# line_kick.net
KiCad netlist of a schematic drawn in EAGLE
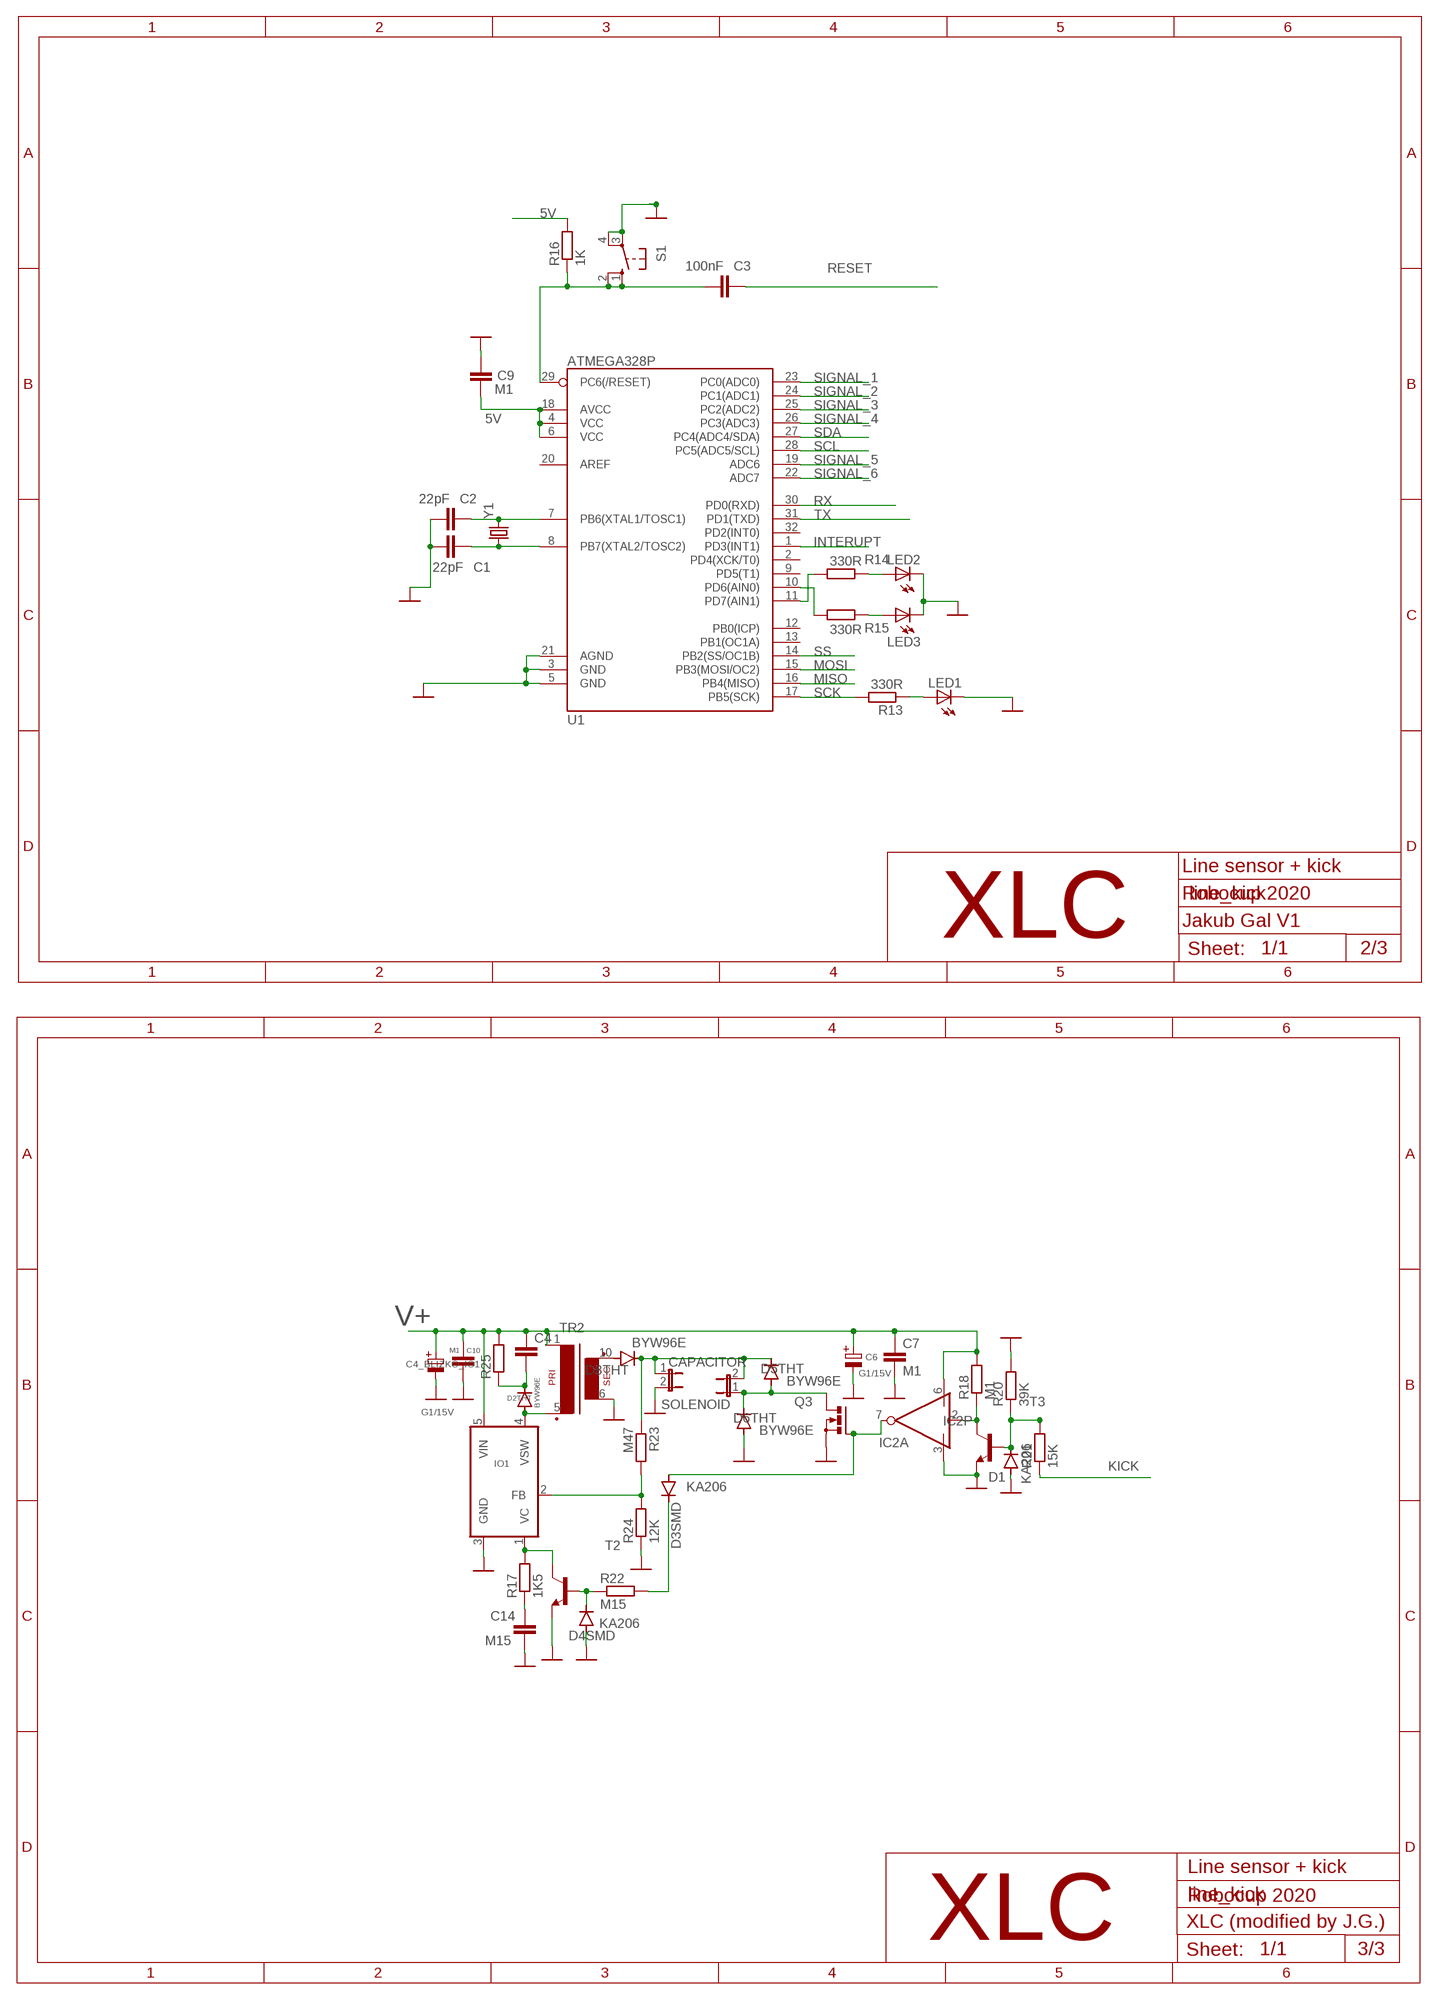
[diagram p0: schematic, sheet 1, part 1 of 2]
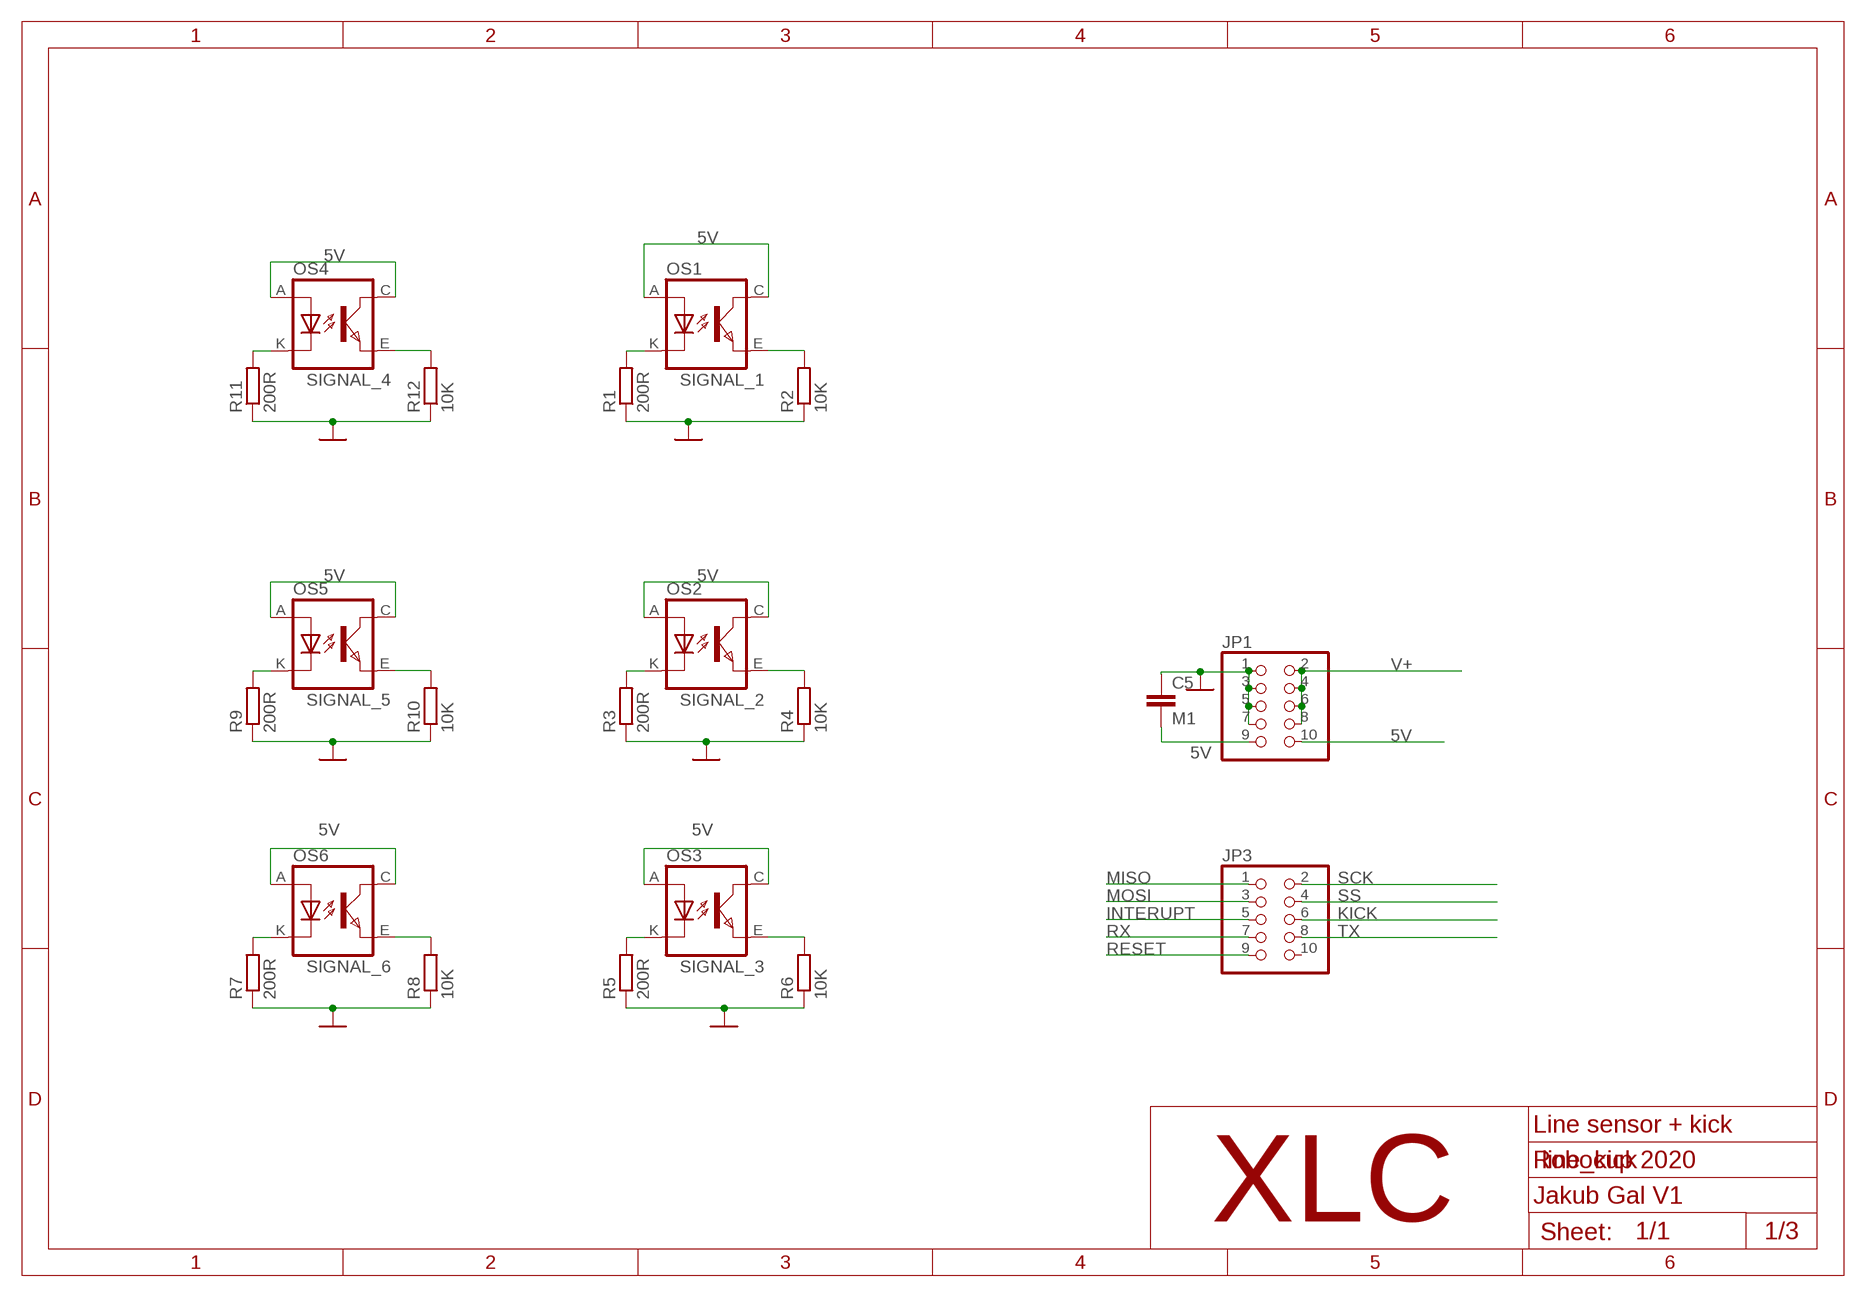
[diagram p1: schematic, sheet 1, part 2 of 2]

(export (version "E")
  (design (tool "Eeschema 10.0.6"))
  (components
    (comp (ref "C1")
      (value "22pF")
      (footprint "eagle-import:C0603")
      (libsource (lib "eagle-import") (part "C-EUC0603"))
    )
    (comp (ref "C2")
      (value "22pF")
      (footprint "eagle-import:C0603")
      (libsource (lib "eagle-import") (part "C-EUC0603"))
    )
    (comp (ref "C3")
      (value "100nF")
      (footprint "eagle-import:C0603")
      (libsource (lib "eagle-import") (part "C-EUC0603"))
    )
    (comp (ref "C4")
      (value "C-EU075-052X106")
      (footprint "eagle-import:C075-052X106")
      (libsource (lib "eagle-import") (part "rcl_334_C-EU075-052X106"))
    )
    (comp (ref "C4_BLIZKO_IO1")
      (value "G1/15V")
      (footprint "eagle-import:E-2,5_7-RAD")
      (libsource (lib "eagle-import") (part "KOND-ELEKT-2,5/7"))
    )
    (comp (ref "C5")
      (value "M1")
      (footprint "eagle-import:C0603")
      (libsource (lib "eagle-import") (part "rcl_334_C-EUC0603"))
    )
    (comp (ref "C6")
      (value "G1/15V")
      (footprint "eagle-import:E-2,5_7-RAD")
      (libsource (lib "eagle-import") (part "KOND-ELEKT-2,5/7"))
    )
    (comp (ref "C7")
      (value "M1")
      (footprint "eagle-import:C0805K")
      (libsource (lib "eagle-import") (part "resistor_348_C-EUC0805K"))
    )
    (comp (ref "C9")
      (value "M1")
      (footprint "eagle-import:C0603")
      (libsource (lib "eagle-import") (part "C-EUC0603"))
    )
    (comp (ref "C10")
      (value "M1")
      (footprint "eagle-import:C0805K")
      (libsource (lib "eagle-import") (part "resistor_348_C-EUC0805K"))
    )
    (comp (ref "C14")
      (value "M15")
      (footprint "eagle-import:C0805K")
      (libsource (lib "eagle-import") (part "resistor_348_C-EUC0805K"))
    )
    (comp (ref "CAPACITOR")
      (value "JP1E")
      (footprint "eagle-import:JP1")
      (libsource (lib "eagle-import") (part "JP1E"))
    )
    (comp (ref "D1")
      (value "KA206")
      (footprint "eagle-import:D-7.5")
      (libsource (lib "eagle-import") (part "DIODE-D-7.5"))
    )
    (comp (ref "D2THT")
      (value "BYW96E")
      (footprint "eagle-import:SOD64-10")
      (libsource (lib "eagle-import") (part "BYW96"))
    )
    (comp (ref "D3SMD")
      (value "KA206")
      (footprint "eagle-import:D-7.5")
      (libsource (lib "eagle-import") (part "DIODE-D-7.5"))
    )
    (comp (ref "D4SMD")
      (value "KA206")
      (footprint "eagle-import:D-7.5")
      (libsource (lib "eagle-import") (part "DIODE-D-7.5"))
    )
    (comp (ref "D5THT")
      (value "BYW96E")
      (footprint "eagle-import:SOD64-10")
      (libsource (lib "eagle-import") (part "BYW96"))
    )
    (comp (ref "D6THT")
      (value "BYW96E")
      (footprint "eagle-import:SOD64-10")
      (libsource (lib "eagle-import") (part "BYW96"))
    )
    (comp (ref "D8THT")
      (value "BYW96E")
      (footprint "eagle-import:SOD64-10")
      (libsource (lib "eagle-import") (part "BYW96"))
    )
    (comp (ref "IC2")
      (value "MIC4423BM")
      (footprint "eagle-import:SO08")
      (libsource (lib "eagle-import") (part "MIC4423BM"))
    )
    (comp (ref "IO1")
      (value "LT1071V")
      (footprint "eagle-import:TO220-5P")
      (libsource (lib "eagle-import") (part "LT1071V"))
    )
    (comp (ref "JP1")
      (value "PINHD-2X5IDC")
      (footprint "eagle-import:2X05_IDC")
      (libsource (lib "eagle-import") (part "PINHD-2X5IDC"))
    )
    (comp (ref "JP3")
      (value "PINHD-2X5IDC")
      (footprint "eagle-import:2X05_IDC")
      (libsource (lib "eagle-import") (part "PINHD-2X5IDC"))
    )
    (comp (ref "LED1")
      (value "LEDCHIPLED_0603")
      (footprint "eagle-import:CHIPLED_0603")
      (libsource (lib "eagle-import") (part "LEDCHIPLED_0603"))
    )
    (comp (ref "LED2")
      (value "LEDCHIPLED_0603")
      (footprint "eagle-import:CHIPLED_0603")
      (libsource (lib "eagle-import") (part "LEDCHIPLED_0603"))
    )
    (comp (ref "LED3")
      (value "LEDCHIPLED_0603")
      (footprint "eagle-import:CHIPLED_0603")
      (libsource (lib "eagle-import") (part "LEDCHIPLED_0603"))
    )
    (comp (ref "OS1")
      (value "TCRT5000")
      (footprint "eagle-import:TCRT5000")
      (libsource (lib "eagle-import") (part "TCRT5000"))
    )
    (comp (ref "OS2")
      (value "TCRT5000")
      (footprint "eagle-import:TCRT5000")
      (libsource (lib "eagle-import") (part "TCRT5000"))
    )
    (comp (ref "OS3")
      (value "TCRT5000")
      (footprint "eagle-import:TCRT5000")
      (libsource (lib "eagle-import") (part "TCRT5000"))
    )
    (comp (ref "OS4")
      (value "TCRT5000")
      (footprint "eagle-import:TCRT5000")
      (fields (field (name "SPICEPREFIX") "O"))
      (libsource (lib "eagle-import") (part "TCRT5000"))
    )
    (comp (ref "OS5")
      (value "TCRT5000")
      (footprint "eagle-import:TCRT5000")
      (libsource (lib "eagle-import") (part "TCRT5000"))
    )
    (comp (ref "OS6")
      (value "TCRT5000")
      (footprint "eagle-import:TCRT5000")
      (fields (field (name "SPICEPREFIX") "O"))
      (libsource (lib "eagle-import") (part "TCRT5000"))
    )
    (comp (ref "Q3")
      (value "PMOSFET_NTO220BV")
      (footprint "eagle-import:TO220BV")
      (libsource (lib "eagle-import") (part "PMOSFET_NTO220BV"))
    )
    (comp (ref "R1")
      (value "200R")
      (footprint "eagle-import:R0603")
      (libsource (lib "eagle-import") (part "R-EU_R0603"))
    )
    (comp (ref "R2")
      (value "10K")
      (footprint "eagle-import:R0603")
      (libsource (lib "eagle-import") (part "R-EU_R0603"))
    )
    (comp (ref "R3")
      (value "200R")
      (footprint "eagle-import:R0603")
      (libsource (lib "eagle-import") (part "R-EU_R0603"))
    )
    (comp (ref "R4")
      (value "10K")
      (footprint "eagle-import:R0603")
      (libsource (lib "eagle-import") (part "R-EU_R0603"))
    )
    (comp (ref "R5")
      (value "200R")
      (footprint "eagle-import:R0603")
      (libsource (lib "eagle-import") (part "R-EU_R0603"))
    )
    (comp (ref "R6")
      (value "10K")
      (footprint "eagle-import:R0603")
      (libsource (lib "eagle-import") (part "R-EU_R0603"))
    )
    (comp (ref "R7")
      (value "200R")
      (footprint "eagle-import:R0603")
      (libsource (lib "eagle-import") (part "R-EU_R0603"))
    )
    (comp (ref "R8")
      (value "10K")
      (footprint "eagle-import:R0603")
      (libsource (lib "eagle-import") (part "R-EU_R0603"))
    )
    (comp (ref "R9")
      (value "200R")
      (footprint "eagle-import:R0603")
      (libsource (lib "eagle-import") (part "R-EU_R0603"))
    )
    (comp (ref "R10")
      (value "10K")
      (footprint "eagle-import:R0603")
      (libsource (lib "eagle-import") (part "R-EU_R0603"))
    )
    (comp (ref "R11")
      (value "200R")
      (footprint "eagle-import:R0603")
      (libsource (lib "eagle-import") (part "R-EU_R0603"))
    )
    (comp (ref "R12")
      (value "10K")
      (footprint "eagle-import:R0603")
      (libsource (lib "eagle-import") (part "R-EU_R0603"))
    )
    (comp (ref "R13")
      (value "330R")
      (footprint "eagle-import:R0603")
      (libsource (lib "eagle-import") (part "R-EU_R0603"))
    )
    (comp (ref "R14")
      (value "330R")
      (footprint "eagle-import:R0603")
      (libsource (lib "eagle-import") (part "R-EU_R0603"))
    )
    (comp (ref "R15")
      (value "330R")
      (footprint "eagle-import:R0603")
      (libsource (lib "eagle-import") (part "R-EU_R0603"))
    )
    (comp (ref "R16")
      (value "1K")
      (footprint "eagle-import:R0603")
      (libsource (lib "eagle-import") (part "R-EU_R0603"))
    )
    (comp (ref "R17")
      (value "1K5")
      (footprint "eagle-import:R1206")
      (libsource (lib "eagle-import") (part "R-EU_R1206"))
    )
    (comp (ref "R18")
      (value "M1")
      (footprint "eagle-import:R1206")
      (libsource (lib "eagle-import") (part "R-EU_R1206"))
    )
    (comp (ref "R20")
      (value "39K")
      (footprint "eagle-import:R1206")
      (libsource (lib "eagle-import") (part "R-EU_R1206"))
    )
    (comp (ref "R21")
      (value "15K")
      (footprint "eagle-import:R1206")
      (libsource (lib "eagle-import") (part "R-EU_R1206"))
    )
    (comp (ref "R22")
      (value "M15")
      (footprint "eagle-import:R1206")
      (libsource (lib "eagle-import") (part "R-EU_R1206"))
    )
    (comp (ref "R23")
      (value "M47")
      (footprint "eagle-import:R1206")
      (libsource (lib "eagle-import") (part "R-EU_R1206"))
    )
    (comp (ref "R24")
      (value "12K")
      (footprint "eagle-import:R1206")
      (libsource (lib "eagle-import") (part "R-EU_R1206"))
    )
    (comp (ref "R25")
      (value "REZISTOR-7,5MM-HORIZ")
      (footprint "eagle-import:R-7,5H")
      (libsource (lib "eagle-import") (part "REZISTOR-7,5MM-HORIZ"))
    )
    (comp (ref "S1")
      (value "10-XX")
      (footprint "eagle-import:B3F-10XX")
      (fields (field (name "MPN") "B3F-1000"))
      (libsource (lib "eagle-import") (part "10-XX"))
    )
    (comp (ref "SOLENOID")
      (value "JP1E")
      (footprint "eagle-import:JP1")
      (libsource (lib "eagle-import") (part "JP1E"))
    )
    (comp (ref "T2")
      (value "-NPN-SC59-BEC")
      (footprint "eagle-import:SC59-BEC")
      (libsource (lib "eagle-import") (part "-NPN-SC59-BEC"))
    )
    (comp (ref "T3")
      (value "-NPN-SC59-BEC")
      (footprint "eagle-import:SC59-BEC")
      (libsource (lib "eagle-import") (part "-NPN-SC59-BEC"))
    )
    (comp (ref "TR2")
      (value "TRAFO-E10-R\"\"")
      (footprint "eagle-import:TRAFO-EE17X20")
      (libsource (lib "eagle-import") (part "TRAFO-E10-R{dblquote}{dblquote}"))
    )
    (comp (ref "U1")
      (value "ATMEGA328P")
      (footprint "eagle-import:TQFP32-08")
      (libsource (lib "eagle-import") (part "ATMEGA328_SMT"))
    )
    (comp (ref "Y1")
      (value "CRYSTALHC49US")
      (footprint "eagle-import:HC49US")
      (libsource (lib "eagle-import") (part "CRYSTALHC49US"))
    )
  )
  (nets
    (net (code "1") (name "/5V") (class "Default")
      (node (ref "C5") (pin "2") (pinfunction "2_2") (pintype "passive"))
      (node (ref "C9") (pin "1") (pinfunction "1_1") (pintype "passive"))
      (node (ref "JP1") (pin "10") (pinfunction "10_10") (pintype "passive"))
      (node (ref "JP1") (pin "9") (pinfunction "9_9") (pintype "passive"))
      (node (ref "OS1") (pin "A") (pinfunction "ANODE_A") (pintype "passive"))
      (node (ref "OS1") (pin "C") (pinfunction "COLLECTOR_C") (pintype "passive"))
      (node (ref "OS2") (pin "A") (pinfunction "ANODE_A") (pintype "passive"))
      (node (ref "OS2") (pin "C") (pinfunction "COLLECTOR_C") (pintype "passive"))
      (node (ref "OS3") (pin "A") (pinfunction "ANODE_A") (pintype "passive"))
      (node (ref "OS3") (pin "C") (pinfunction "COLLECTOR_C") (pintype "passive"))
      (node (ref "OS4") (pin "A") (pinfunction "ANODE_A") (pintype "passive"))
      (node (ref "OS4") (pin "C") (pinfunction "COLLECTOR_C") (pintype "passive"))
      (node (ref "OS5") (pin "A") (pinfunction "ANODE_A") (pintype "passive"))
      (node (ref "OS5") (pin "C") (pinfunction "COLLECTOR_C") (pintype "passive"))
      (node (ref "OS6") (pin "A") (pinfunction "ANODE_A") (pintype "passive"))
      (node (ref "OS6") (pin "C") (pinfunction "COLLECTOR_C") (pintype "passive"))
      (node (ref "R16") (pin "2") (pinfunction "2_2") (pintype "passive"))
      (node (ref "U1") (pin "18") (pinfunction "AVCC_18") (pintype "bidirectional"))
      (node (ref "U1") (pin "4") (pinfunction "VCC_4") (pintype "bidirectional"))
      (node (ref "U1") (pin "6") (pinfunction "VCC_6") (pintype "bidirectional"))
    )
    (net (code "2") (name "/INTERUPT") (class "Default")
      (node (ref "JP3") (pin "5") (pinfunction "5_5") (pintype "passive"))
      (node (ref "U1") (pin "1") (pinfunction "PD3(INT1)_1") (pintype "bidirectional"))
    )
    (net (code "3") (name "/KICK") (class "Default")
      (node (ref "JP3") (pin "6") (pinfunction "6_6") (pintype "passive"))
      (node (ref "R21") (pin "1") (pinfunction "1_1") (pintype "passive"))
    )
    (net (code "4") (name "/MISO") (class "Default")
      (node (ref "JP3") (pin "1") (pinfunction "1_1") (pintype "passive"))
      (node (ref "U1") (pin "16") (pinfunction "PB4(MISO)_16") (pintype "bidirectional"))
    )
    (net (code "5") (name "/MOSI") (class "Default")
      (node (ref "JP3") (pin "3") (pinfunction "3_3") (pintype "passive"))
      (node (ref "U1") (pin "15") (pinfunction "PB3(MOSI/OC2)_15") (pintype "bidirectional"))
    )
    (net (code "6") (name "/RESET") (class "Default")
      (node (ref "C3") (pin "2") (pinfunction "2_2") (pintype "passive"))
      (node (ref "JP3") (pin "9") (pinfunction "9_9") (pintype "passive"))
    )
    (net (code "7") (name "/RX") (class "Default")
      (node (ref "JP3") (pin "7") (pinfunction "7_7") (pintype "passive"))
      (node (ref "U1") (pin "30") (pinfunction "PD0(RXD)_30") (pintype "bidirectional"))
    )
    (net (code "8") (name "/SCK") (class "Default")
      (node (ref "JP3") (pin "2") (pinfunction "2_2") (pintype "passive"))
      (node (ref "R13") (pin "2") (pinfunction "2_2") (pintype "passive"))
      (node (ref "U1") (pin "17") (pinfunction "PB5(SCK)_17") (pintype "bidirectional"))
    )
    (net (code "9") (name "/SCL") (class "Default")
      (node (ref "U1") (pin "28") (pinfunction "PC5(ADC5/SCL)_28") (pintype "bidirectional"))
    )
    (net (code "10") (name "/SDA") (class "Default")
      (node (ref "U1") (pin "27") (pinfunction "PC4(ADC4/SDA)_27") (pintype "bidirectional"))
    )
    (net (code "11") (name "/SIGNAL_1") (class "Default")
      (node (ref "OS1") (pin "E") (pinfunction "EMITTER_E") (pintype "passive"))
      (node (ref "R2") (pin "2") (pinfunction "2_2") (pintype "passive"))
      (node (ref "U1") (pin "23") (pinfunction "PC0(ADC0)_23") (pintype "bidirectional"))
    )
    (net (code "12") (name "/SIGNAL_2") (class "Default")
      (node (ref "OS2") (pin "E") (pinfunction "EMITTER_E") (pintype "passive"))
      (node (ref "R4") (pin "2") (pinfunction "2_2") (pintype "passive"))
      (node (ref "U1") (pin "24") (pinfunction "PC1(ADC1)_24") (pintype "bidirectional"))
    )
    (net (code "13") (name "/SIGNAL_3") (class "Default")
      (node (ref "OS3") (pin "E") (pinfunction "EMITTER_E") (pintype "passive"))
      (node (ref "R6") (pin "2") (pinfunction "2_2") (pintype "passive"))
      (node (ref "U1") (pin "25") (pinfunction "PC2(ADC2)_25") (pintype "bidirectional"))
    )
    (net (code "14") (name "/SIGNAL_4") (class "Default")
      (node (ref "OS4") (pin "E") (pinfunction "EMITTER_E") (pintype "passive"))
      (node (ref "R12") (pin "2") (pinfunction "2_2") (pintype "passive"))
      (node (ref "U1") (pin "26") (pinfunction "PC3(ADC3)_26") (pintype "bidirectional"))
    )
    (net (code "15") (name "/SIGNAL_5") (class "Default")
      (node (ref "OS5") (pin "E") (pinfunction "EMITTER_E") (pintype "passive"))
      (node (ref "R10") (pin "2") (pinfunction "2_2") (pintype "passive"))
      (node (ref "U1") (pin "19") (pinfunction "ADC6_19") (pintype "bidirectional"))
    )
    (net (code "16") (name "/SIGNAL_6") (class "Default")
      (node (ref "OS6") (pin "E") (pinfunction "EMITTER_E") (pintype "passive"))
      (node (ref "R8") (pin "2") (pinfunction "2_2") (pintype "passive"))
      (node (ref "U1") (pin "22") (pinfunction "ADC7_22") (pintype "bidirectional"))
    )
    (net (code "17") (name "/SS") (class "Default")
      (node (ref "JP3") (pin "4") (pinfunction "4_4") (pintype "passive"))
      (node (ref "U1") (pin "14") (pinfunction "PB2(SS/OC1B)_14") (pintype "bidirectional"))
    )
    (net (code "18") (name "/TX") (class "Default")
      (node (ref "JP3") (pin "8") (pinfunction "8_8") (pintype "passive"))
      (node (ref "U1") (pin "31") (pinfunction "PD1(TXD)_31") (pintype "bidirectional"))
    )
    (net (code "19") (name "/V+") (class "Default")
      (node (ref "C10") (pin "1") (pinfunction "1_1") (pintype "passive"))
      (node (ref "C4") (pin "1") (pinfunction "1_1") (pintype "passive"))
      (node (ref "C4_BLIZKO_IO1") (pin "+") (pinfunction "+_+") (pintype "passive"))
      (node (ref "C6") (pin "+") (pinfunction "+_+") (pintype "passive"))
      (node (ref "C7") (pin "1") (pinfunction "1_1") (pintype "passive"))
      (node (ref "IC2") (pin "6") (pinfunction "V+_6") (pintype "power_in"))
      (node (ref "IO1") (pin "5") (pinfunction "VIN_5") (pintype "power_in"))
      (node (ref "JP1") (pin "2") (pinfunction "2_2") (pintype "passive"))
      (node (ref "JP1") (pin "4") (pinfunction "4_4") (pintype "passive"))
      (node (ref "JP1") (pin "6") (pinfunction "6_6") (pintype "passive"))
      (node (ref "JP1") (pin "8") (pinfunction "8_8") (pintype "passive"))
      (node (ref "R18") (pin "2") (pinfunction "2_2") (pintype "passive"))
      (node (ref "R25") (pin "2") (pinfunction "2_2") (pintype "passive"))
      (node (ref "TR2") (pin "1") (pinfunction "1_1") (pintype "passive"))
    )
    (net (code "20") (name "GND") (class "Default")
      (node (ref "C1") (pin "1") (pinfunction "1_1") (pintype "passive"))
      (node (ref "C10") (pin "2") (pinfunction "2_2") (pintype "passive"))
      (node (ref "C14") (pin "2") (pinfunction "2_2") (pintype "passive"))
      (node (ref "C2") (pin "1") (pinfunction "1_1") (pintype "passive"))
      (node (ref "C4_BLIZKO_IO1") (pin "-") (pinfunction "-_-") (pintype "passive"))
      (node (ref "C5") (pin "1") (pinfunction "1_1") (pintype "passive"))
      (node (ref "C6") (pin "-") (pinfunction "-_-") (pintype "passive"))
      (node (ref "C7") (pin "2") (pinfunction "2_2") (pintype "passive"))
      (node (ref "C9") (pin "2") (pinfunction "2_2") (pintype "passive"))
      (node (ref "CAPACITOR") (pin "2") (pinfunction "2_2") (pintype "passive"))
      (node (ref "D1") (pin "A") (pinfunction "A_A") (pintype "passive"))
      (node (ref "D4SMD") (pin "A") (pinfunction "A_A") (pintype "passive"))
      (node (ref "D6THT") (pin "A") (pinfunction "A_A") (pintype "passive"))
      (node (ref "IC2") (pin "3") (pinfunction "GND_3") (pintype "power_in"))
      (node (ref "IO1") (pin "3") (pinfunction "GND_3") (pintype "power_in"))
      (node (ref "JP1") (pin "1") (pinfunction "1_1") (pintype "passive"))
      (node (ref "JP1") (pin "3") (pinfunction "3_3") (pintype "passive"))
      (node (ref "JP1") (pin "5") (pinfunction "5_5") (pintype "passive"))
      (node (ref "JP1") (pin "7") (pinfunction "7_7") (pintype "passive"))
      (node (ref "LED1") (pin "C") (pinfunction "C_C") (pintype "passive"))
      (node (ref "LED2") (pin "C") (pinfunction "C_C") (pintype "passive"))
      (node (ref "LED3") (pin "C") (pinfunction "C_C") (pintype "passive"))
      (node (ref "Q3") (pin "S") (pinfunction "S_S") (pintype "passive"))
      (node (ref "R1") (pin "1") (pinfunction "1_1") (pintype "passive"))
      (node (ref "R10") (pin "1") (pinfunction "1_1") (pintype "passive"))
      (node (ref "R11") (pin "1") (pinfunction "1_1") (pintype "passive"))
      (node (ref "R12") (pin "1") (pinfunction "1_1") (pintype "passive"))
      (node (ref "R2") (pin "1") (pinfunction "1_1") (pintype "passive"))
      (node (ref "R20") (pin "2") (pinfunction "2_2") (pintype "passive"))
      (node (ref "R24") (pin "1") (pinfunction "1_1") (pintype "passive"))
      (node (ref "R3") (pin "1") (pinfunction "1_1") (pintype "passive"))
      (node (ref "R4") (pin "1") (pinfunction "1_1") (pintype "passive"))
      (node (ref "R5") (pin "1") (pinfunction "1_1") (pintype "passive"))
      (node (ref "R6") (pin "1") (pinfunction "1_1") (pintype "passive"))
      (node (ref "R7") (pin "1") (pinfunction "1_1") (pintype "passive"))
      (node (ref "R8") (pin "1") (pinfunction "1_1") (pintype "passive"))
      (node (ref "R9") (pin "1") (pinfunction "1_1") (pintype "passive"))
      (node (ref "S1") (pin "3") (pinfunction "P_3") (pintype "passive"))
      (node (ref "S1") (pin "4") (pinfunction "P1_4") (pintype "passive"))
      (node (ref "T2") (pin "E") (pinfunction "E_E") (pintype "passive"))
      (node (ref "T3") (pin "E") (pinfunction "E_E") (pintype "passive"))
      (node (ref "TR2") (pin "6") (pinfunction "3_6") (pintype "passive"))
      (node (ref "U1") (pin "21") (pinfunction "AGND_21") (pintype "bidirectional"))
      (node (ref "U1") (pin "3") (pinfunction "GND_3") (pintype "bidirectional"))
      (node (ref "U1") (pin "5") (pinfunction "GND_5") (pintype "bidirectional"))
    )
    (net (code "21") (name "Net-(C4-Pad2)") (class "Default")
      (node (ref "C4") (pin "2") (pinfunction "2_2") (pintype "passive"))
      (node (ref "D2THT") (pin "C") (pinfunction "C_C") (pintype "passive"))
      (node (ref "R25") (pin "1") (pinfunction "1_1") (pintype "passive"))
    )
    (net (code "22") (name "Net-(C14-Pad1)") (class "Default")
      (node (ref "C14") (pin "1") (pinfunction "1_1") (pintype "passive"))
      (node (ref "R17") (pin "1") (pinfunction "1_1") (pintype "passive"))
    )
    (net (code "23") (name "Net-(CAPACITOR-Pad1)") (class "Default")
      (node (ref "CAPACITOR") (pin "1") (pinfunction "1_1") (pintype "passive"))
      (node (ref "D5THT") (pin "C") (pinfunction "C_C") (pintype "passive"))
      (node (ref "D8THT") (pin "C") (pinfunction "C_C") (pintype "passive"))
      (node (ref "R23") (pin "1") (pinfunction "1_1") (pintype "passive"))
      (node (ref "SOLENOID") (pin "2") (pinfunction "2_2") (pintype "passive"))
    )
    (net (code "24") (name "Net-(D1-PadC)") (class "Default")
      (node (ref "D1") (pin "C") (pinfunction "C_C") (pintype "passive"))
      (node (ref "R20") (pin "1") (pinfunction "1_1") (pintype "passive"))
      (node (ref "R21") (pin "2") (pinfunction "2_2") (pintype "passive"))
      (node (ref "T3") (pin "B") (pinfunction "B_B") (pintype "passive"))
    )
    (net (code "25") (name "Net-(D3SMD-PadC)") (class "Default")
      (node (ref "D3SMD") (pin "C") (pinfunction "C_C") (pintype "passive"))
      (node (ref "R22") (pin "2") (pinfunction "2_2") (pintype "passive"))
    )
    (net (code "26") (name "Net-(D4SMD-PadC)") (class "Default")
      (node (ref "D4SMD") (pin "C") (pinfunction "C_C") (pintype "passive"))
      (node (ref "R22") (pin "1") (pinfunction "1_1") (pintype "passive"))
      (node (ref "T2") (pin "B") (pinfunction "B_B") (pintype "passive"))
    )
    (net (code "27") (name "Net-(D5THT-PadA)") (class "Default")
      (node (ref "D5THT") (pin "A") (pinfunction "A_A") (pintype "passive"))
      (node (ref "D6THT") (pin "C") (pinfunction "C_C") (pintype "passive"))
      (node (ref "Q3") (pin "D") (pinfunction "D_D") (pintype "passive"))
      (node (ref "SOLENOID") (pin "1") (pinfunction "1_1") (pintype "passive"))
    )
    (net (code "28") (name "Net-(IC2A-IN)") (class "Default")
      (node (ref "IC2") (pin "2") (pinfunction "IN_2") (pintype "input"))
      (node (ref "R18") (pin "1") (pinfunction "1_1") (pintype "passive"))
      (node (ref "T3") (pin "C") (pinfunction "C_C") (pintype "passive"))
    )
    (net (code "29") (name "Net-(IC2A-OUT)") (class "Default")
      (node (ref "D3SMD") (pin "A") (pinfunction "A_A") (pintype "passive"))
      (node (ref "IC2") (pin "7") (pinfunction "OUT_7") (pintype "output"))
      (node (ref "Q3") (pin "G") (pinfunction "G_G") (pintype "passive"))
    )
    (net (code "30") (name "Net-(IO1-FB)") (class "Default")
      (node (ref "IO1") (pin "2") (pinfunction "FB_2") (pintype "input"))
      (node (ref "R23") (pin "2") (pinfunction "2_2") (pintype "passive"))
      (node (ref "R24") (pin "2") (pinfunction "2_2") (pintype "passive"))
    )
    (net (code "31") (name "Net-(IO1-VC)") (class "Default")
      (node (ref "IO1") (pin "1") (pinfunction "VC_1") (pintype "input"))
      (node (ref "R17") (pin "2") (pinfunction "2_2") (pintype "passive"))
      (node (ref "T2") (pin "C") (pinfunction "C_C") (pintype "passive"))
    )
    (net (code "32") (name "Net-(IO1-VSW)") (class "Default")
      (node (ref "D2THT") (pin "A") (pinfunction "A_A") (pintype "passive"))
      (node (ref "IO1") (pin "4") (pinfunction "VSW_4") (pintype "output"))
      (node (ref "TR2") (pin "5") (pinfunction "2_5") (pintype "passive"))
    )
    (net (code "33") (name "Net-(LED1-PadA)") (class "Default")
      (node (ref "LED1") (pin "A") (pinfunction "A_A") (pintype "passive"))
      (node (ref "R13") (pin "1") (pinfunction "1_1") (pintype "passive"))
    )
    (net (code "34") (name "Net-(LED2-PadA)") (class "Default")
      (node (ref "LED2") (pin "A") (pinfunction "A_A") (pintype "passive"))
      (node (ref "R14") (pin "1") (pinfunction "1_1") (pintype "passive"))
    )
    (net (code "35") (name "Net-(LED3-PadA)") (class "Default")
      (node (ref "LED3") (pin "A") (pinfunction "A_A") (pintype "passive"))
      (node (ref "R15") (pin "1") (pinfunction "1_1") (pintype "passive"))
    )
    (net (code "36") (name "Net-(OS1-CATHODE)") (class "Default")
      (node (ref "OS1") (pin "K") (pinfunction "CATHODE_K") (pintype "passive"))
      (node (ref "R1") (pin "2") (pinfunction "2_2") (pintype "passive"))
    )
    (net (code "37") (name "Net-(OS2-CATHODE)") (class "Default")
      (node (ref "OS2") (pin "K") (pinfunction "CATHODE_K") (pintype "passive"))
      (node (ref "R3") (pin "2") (pinfunction "2_2") (pintype "passive"))
    )
    (net (code "38") (name "Net-(OS3-CATHODE)") (class "Default")
      (node (ref "OS3") (pin "K") (pinfunction "CATHODE_K") (pintype "passive"))
      (node (ref "R5") (pin "2") (pinfunction "2_2") (pintype "passive"))
    )
    (net (code "39") (name "Net-(OS4-CATHODE)") (class "Default")
      (node (ref "OS4") (pin "K") (pinfunction "CATHODE_K") (pintype "passive"))
      (node (ref "R11") (pin "2") (pinfunction "2_2") (pintype "passive"))
    )
    (net (code "40") (name "Net-(OS5-CATHODE)") (class "Default")
      (node (ref "OS5") (pin "K") (pinfunction "CATHODE_K") (pintype "passive"))
      (node (ref "R9") (pin "2") (pinfunction "2_2") (pintype "passive"))
    )
    (net (code "41") (name "Net-(OS6-CATHODE)") (class "Default")
      (node (ref "OS6") (pin "K") (pinfunction "CATHODE_K") (pintype "passive"))
      (node (ref "R7") (pin "2") (pinfunction "2_2") (pintype "passive"))
    )
    (net (code "42") (name "Net-(S1-S)") (class "Default")
      (node (ref "C3") (pin "1") (pinfunction "1_1") (pintype "passive"))
      (node (ref "R16") (pin "1") (pinfunction "1_1") (pintype "passive"))
      (node (ref "S1") (pin "1") (pinfunction "S_1") (pintype "passive"))
      (node (ref "S1") (pin "2") (pinfunction "S1_2") (pintype "passive"))
      (node (ref "U1") (pin "29") (pinfunction "PC6(/RESET)_29") (pintype "bidirectional"))
    )
    (net (code "43") (name "Net-(TR2-4)") (class "Default")
      (node (ref "D8THT") (pin "A") (pinfunction "A_A") (pintype "passive"))
      (node (ref "TR2") (pin "10") (pinfunction "4_10") (pintype "passive"))
    )
    (net (code "44") (name "Net-(U1-PB6(XTAL1{slash}TOSC1))") (class "Default")
      (node (ref "C2") (pin "2") (pinfunction "2_2") (pintype "passive"))
      (node (ref "U1") (pin "7") (pinfunction "PB6(XTAL1/TOSC1)_7") (pintype "bidirectional"))
      (node (ref "Y1") (pin "2") (pinfunction "2_2") (pintype "passive"))
    )
    (net (code "45") (name "Net-(U1-PB7(XTAL2{slash}TOSC2))") (class "Default")
      (node (ref "C1") (pin "2") (pinfunction "2_2") (pintype "passive"))
      (node (ref "U1") (pin "8") (pinfunction "PB7(XTAL2/TOSC2)_8") (pintype "bidirectional"))
      (node (ref "Y1") (pin "1") (pinfunction "1_1") (pintype "passive"))
    )
    (net (code "46") (name "Net-(U1-PD6(AIN0))") (class "Default")
      (node (ref "R15") (pin "2") (pinfunction "2_2") (pintype "passive"))
      (node (ref "U1") (pin "10") (pinfunction "PD6(AIN0)_10") (pintype "bidirectional"))
    )
    (net (code "47") (name "Net-(U1-PD7(AIN1))") (class "Default")
      (node (ref "R14") (pin "2") (pinfunction "2_2") (pintype "passive"))
      (node (ref "U1") (pin "11") (pinfunction "PD7(AIN1)_11") (pintype "bidirectional"))
    )
    (net (code "48") (name "unconnected-(JP3-Pad10)") (class "Default")
      (node (ref "JP3") (pin "10") (pinfunction "10_10") (pintype "passive"))
    )
    (net (code "49") (name "unconnected-(U1-AREF-Pad20)") (class "Default")
      (node (ref "U1") (pin "20") (pinfunction "AREF_20") (pintype "bidirectional"))
    )
    (net (code "50") (name "unconnected-(U1-PB0(ICP)-Pad12)") (class "Default")
      (node (ref "U1") (pin "12") (pinfunction "PB0(ICP)_12") (pintype "bidirectional"))
    )
    (net (code "51") (name "unconnected-(U1-PB1(OC1A)-Pad13)") (class "Default")
      (node (ref "U1") (pin "13") (pinfunction "PB1(OC1A)_13") (pintype "bidirectional"))
    )
    (net (code "52") (name "unconnected-(U1-PD2(INT0)-Pad32)") (class "Default")
      (node (ref "U1") (pin "32") (pinfunction "PD2(INT0)_32") (pintype "bidirectional"))
    )
    (net (code "53") (name "unconnected-(U1-PD4(XCK{slash}T0)-Pad2)") (class "Default")
      (node (ref "U1") (pin "2") (pinfunction "PD4(XCK/T0)_2") (pintype "bidirectional"))
    )
    (net (code "54") (name "unconnected-(U1-PD5(T1)-Pad9)") (class "Default")
      (node (ref "U1") (pin "9") (pinfunction "PD5(T1)_9") (pintype "bidirectional"))
    )
  )
)
